# Connector.net
KiCad netlist of a schematic drawn in Altium Designer
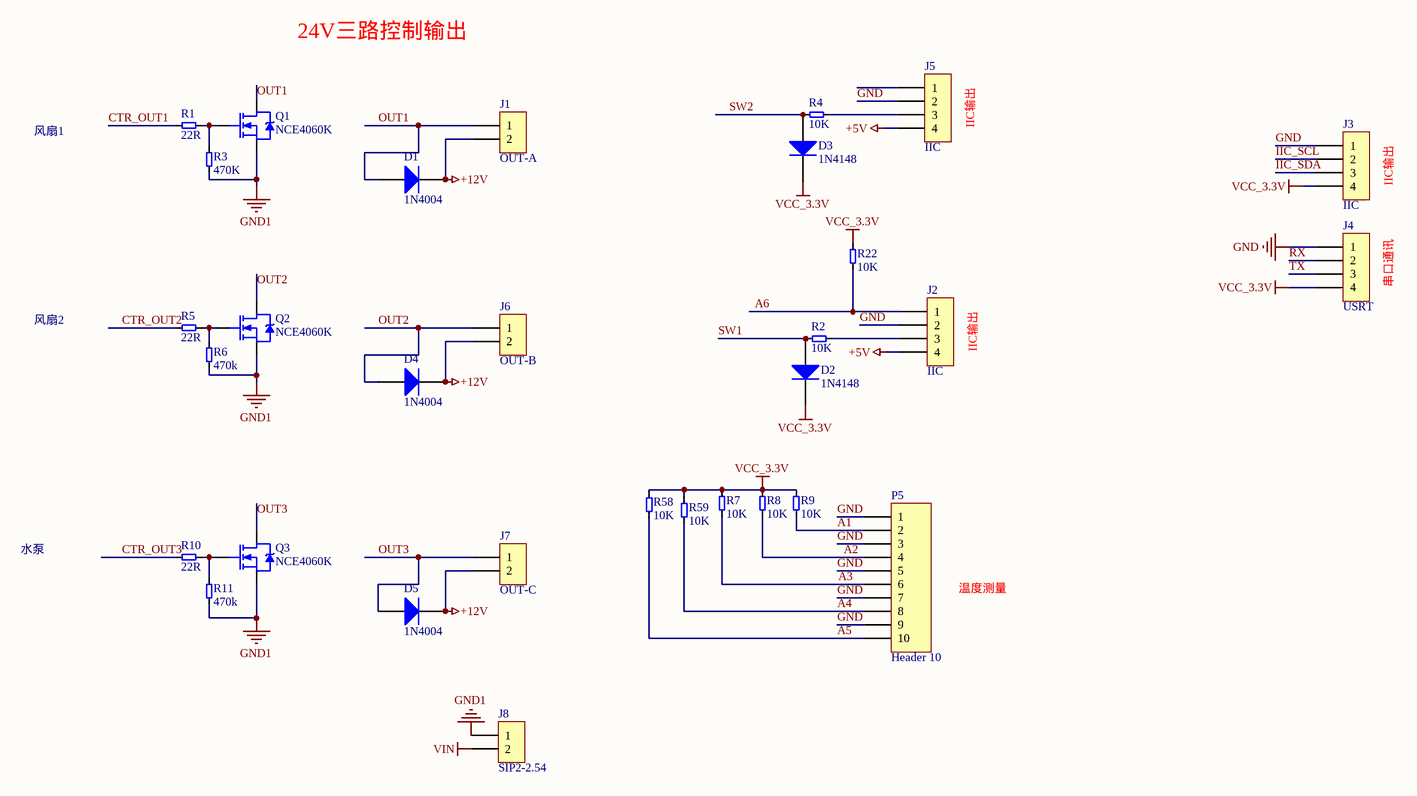
[diagram p0: Connector.SchDoc]

(export (version "E")
  (design (tool "Eeschema 10.0.6"))
  (components
    (comp (ref "D1")
      (value "1N4004")
      (footprint "D7227")
      (description "Default Diode")
      (fields (field (name "PUBLISHER") "Altium Limited"))
      (libsource (lib "SM") (part "Diode_2"))
    )
    (comp (ref "D2")
      (value "1N4148")
      (footprint "sod323")
      (description "Default Diode")
      (fields (field (name "PUBLISHER") "Altium Limited"))
      (libsource (lib "Miscellaneous Devices") (part "Diode"))
    )
    (comp (ref "D3")
      (value "1N4148")
      (footprint "sod323")
      (description "Default Diode")
      (fields (field (name "PUBLISHER") "Altium Limited"))
      (libsource (lib "Miscellaneous Devices") (part "Diode"))
    )
    (comp (ref "D4")
      (value "1N4004")
      (footprint "D7227")
      (description "Default Diode")
      (fields (field (name "PUBLISHER") "Altium Limited"))
      (libsource (lib "SM") (part "Diode_2"))
    )
    (comp (ref "D5")
      (value "1N4004")
      (footprint "D7227")
      (description "Default Diode")
      (fields (field (name "PUBLISHER") "Altium Limited"))
      (libsource (lib "SM") (part "Diode_2"))
    )
    (comp (ref "J1")
      (value "OUT-A")
      (footprint "CH3.96-2P")
      (description "Connector")
      (libsource (lib "SM") (part "CON2"))
    )
    (comp (ref "J2")
      (value "IIC")
      (footprint "SIP-4L")
      (description "CN-SIP4-2.54")
      (libsource (lib "接插件") (part "SIP4-2.54"))
    )
    (comp (ref "J3")
      (value "IIC")
      (footprint "SIP-4L")
      (description "CN-SIP4-2.54")
      (libsource (lib "接插件") (part "SIP4-2.54"))
    )
    (comp (ref "J4")
      (value "USRT")
      (footprint "SIP-4L")
      (description "CN-SIP4-2.54")
      (libsource (lib "接插件") (part "SIP4-2.54"))
    )
    (comp (ref "J5")
      (value "IIC")
      (footprint "SIP-4L")
      (description "CN-SIP4-2.54")
      (libsource (lib "接插件") (part "SIP4-2.54"))
    )
    (comp (ref "J6")
      (value "OUT-B")
      (footprint "CH3.96-2P")
      (description "Connector")
      (libsource (lib "SM") (part "CON2"))
    )
    (comp (ref "J7")
      (value "OUT-C")
      (footprint "CH3.96-2P")
      (description "Connector")
      (libsource (lib "SM") (part "CON2"))
    )
    (comp (ref "J8")
      (value "SIP2-2.54")
      (footprint "CH3.96-2P")
      (description "CN-SIP2-2.54")
      (libsource (lib "接插件") (part "SIP2-2.54"))
    )
    (comp (ref "P5")
      (value "Header 10")
      (footprint "SIP-10L")
      (description "Header, 10-Pin")
      (fields (field (name "PUBLISHER") "Altium Limited"))
      (libsource (lib "Miscellaneous Connectors") (part "Header 10"))
    )
    (comp (ref "Q1")
      (value "NCE4060K")
      (footprint "TO-252-3S")
      (description "NMOSFET")
      (libsource (lib "SM") (part "NCE4060K"))
    )
    (comp (ref "Q2")
      (value "NCE4060K")
      (footprint "TO-252-3S")
      (description "NMOSFET")
      (libsource (lib "SM") (part "NCE4060K"))
    )
    (comp (ref "Q3")
      (value "NCE4060K")
      (footprint "TO-252-3S")
      (description "NMOSFET")
      (libsource (lib "SM") (part "NCE4060K"))
    )
    (comp (ref "R1")
      (value "22R")
      (footprint "0805R")
      (description "CR85-102J")
      (libsource (lib "SMD电阻") (part "1K"))
    )
    (comp (ref "R2")
      (value "10K")
      (footprint "0805R")
      (description "CR85-102J")
      (libsource (lib "SMD电阻") (part "1K"))
    )
    (comp (ref "R3")
      (value "470K")
      (footprint "0805R")
      (description "CR85-102J")
      (libsource (lib "SMD电阻") (part "1K"))
    )
    (comp (ref "R4")
      (value "10K")
      (footprint "0805R")
      (description "CR85-102J")
      (libsource (lib "SMD电阻") (part "1K"))
    )
    (comp (ref "R5")
      (value "22R")
      (footprint "0805R")
      (description "CR85-102J")
      (libsource (lib "SMD电阻") (part "1K"))
    )
    (comp (ref "R6")
      (value "470k")
      (footprint "0805R")
      (description "CR85-102J")
      (libsource (lib "SMD电阻") (part "1K"))
    )
    (comp (ref "R7")
      (value "10K")
      (footprint "0805R")
      (description "CR85-102J")
      (libsource (lib "SMD电阻") (part "1K"))
    )
    (comp (ref "R8")
      (value "10K")
      (footprint "0805R")
      (description "CR85-102J")
      (libsource (lib "SMD电阻") (part "1K"))
    )
    (comp (ref "R9")
      (value "10K")
      (footprint "0805R")
      (description "CR85-102J")
      (libsource (lib "SMD电阻") (part "1K"))
    )
    (comp (ref "R10")
      (value "22R")
      (footprint "0805R")
      (description "CR85-102J")
      (libsource (lib "SMD电阻") (part "1K"))
    )
    (comp (ref "R11")
      (value "470k")
      (footprint "0805R")
      (description "CR85-102J")
      (libsource (lib "SMD电阻") (part "1K"))
    )
    (comp (ref "R22")
      (value "10K")
      (footprint "0805R")
      (description "CR85-102J")
      (libsource (lib "SMD电阻") (part "1K"))
    )
    (comp (ref "R58")
      (value "10K")
      (footprint "0805R")
      (description "CR85-102J")
      (libsource (lib "SMD电阻") (part "1K"))
    )
    (comp (ref "R59")
      (value "10K")
      (footprint "0805R")
      (description "CR85-102J")
      (libsource (lib "SMD电阻") (part "1K"))
    )
  )
  (nets
    (net (code "1") (name "+5V") (class "Default")
      (node (ref "J2") (pin "4") (pinfunction "4_4") (pintype "passive"))
      (node (ref "J5") (pin "4") (pinfunction "4_4") (pintype "passive"))
    )
    (net (code "2") (name "+12V") (class "Default")
      (node (ref "D1") (pin "K") (pinfunction "K_K") (pintype "passive"))
      (node (ref "D4") (pin "K") (pinfunction "K_K") (pintype "passive"))
      (node (ref "D5") (pin "K") (pinfunction "K_K") (pintype "passive"))
      (node (ref "J1") (pin "2") (pinfunction "2_2") (pintype "passive"))
      (node (ref "J6") (pin "2") (pinfunction "2_2") (pintype "passive"))
      (node (ref "J7") (pin "2") (pinfunction "2_2") (pintype "passive"))
    )
    (net (code "3") (name "/A1") (class "Default")
      (node (ref "P5") (pin "2") (pinfunction "2_2") (pintype "passive"))
      (node (ref "R9") (pin "1") (pinfunction "1_1") (pintype "passive"))
    )
    (net (code "4") (name "/A2") (class "Default")
      (node (ref "P5") (pin "4") (pinfunction "4_4") (pintype "passive"))
      (node (ref "R8") (pin "1") (pinfunction "1_1") (pintype "passive"))
    )
    (net (code "5") (name "/A3") (class "Default")
      (node (ref "P5") (pin "6") (pinfunction "6_6") (pintype "passive"))
      (node (ref "R7") (pin "1") (pinfunction "1_1") (pintype "passive"))
    )
    (net (code "6") (name "/A4") (class "Default")
      (node (ref "P5") (pin "8") (pinfunction "8_8") (pintype "passive"))
      (node (ref "R59") (pin "2") (pinfunction "2_2") (pintype "passive"))
    )
    (net (code "7") (name "/A5") (class "Default")
      (node (ref "P5") (pin "10") (pinfunction "10_10") (pintype "passive"))
      (node (ref "R58") (pin "1") (pinfunction "1_1") (pintype "passive"))
    )
    (net (code "8") (name "/A6") (class "Default")
      (node (ref "J2") (pin "1") (pinfunction "1_1") (pintype "passive"))
      (node (ref "R22") (pin "1") (pinfunction "1_1") (pintype "passive"))
    )
    (net (code "9") (name "/CTR_OUT1") (class "Default")
      (node (ref "R1") (pin "1") (pinfunction "1_1") (pintype "passive"))
    )
    (net (code "10") (name "/CTR_OUT2") (class "Default")
      (node (ref "R5") (pin "1") (pinfunction "1_1") (pintype "passive"))
    )
    (net (code "11") (name "/CTR_OUT3") (class "Default")
      (node (ref "R10") (pin "1") (pinfunction "1_1") (pintype "passive"))
    )
    (net (code "12") (name "/IIC_SCL") (class "Default")
      (node (ref "J3") (pin "2") (pinfunction "2_2") (pintype "passive"))
    )
    (net (code "13") (name "/IIC_SDA") (class "Default")
      (node (ref "J3") (pin "3") (pinfunction "3_3") (pintype "passive"))
    )
    (net (code "14") (name "/OUT1") (class "Default")
      (node (ref "D1") (pin "A") (pinfunction "A_A") (pintype "passive"))
      (node (ref "J1") (pin "1") (pinfunction "1_1") (pintype "passive"))
      (node (ref "Q1") (pin "2") (pinfunction "D_2") (pintype "passive"))
    )
    (net (code "15") (name "/OUT2") (class "Default")
      (node (ref "D4") (pin "A") (pinfunction "A_A") (pintype "passive"))
      (node (ref "J6") (pin "1") (pinfunction "1_1") (pintype "passive"))
      (node (ref "Q2") (pin "2") (pinfunction "D_2") (pintype "passive"))
    )
    (net (code "16") (name "/OUT3") (class "Default")
      (node (ref "D5") (pin "A") (pinfunction "A_A") (pintype "passive"))
      (node (ref "J7") (pin "1") (pinfunction "1_1") (pintype "passive"))
      (node (ref "Q3") (pin "2") (pinfunction "D_2") (pintype "passive"))
    )
    (net (code "17") (name "/RX") (class "Default")
      (node (ref "J4") (pin "2") (pinfunction "2_2") (pintype "passive"))
    )
    (net (code "18") (name "/SW1") (class "Default")
      (node (ref "D2") (pin "A") (pinfunction "A_A") (pintype "passive"))
      (node (ref "R2") (pin "2") (pinfunction "2_2") (pintype "passive"))
    )
    (net (code "19") (name "/SW2") (class "Default")
      (node (ref "D3") (pin "A") (pinfunction "A_A") (pintype "passive"))
      (node (ref "R4") (pin "2") (pinfunction "2_2") (pintype "passive"))
    )
    (net (code "20") (name "/TX") (class "Default")
      (node (ref "J4") (pin "3") (pinfunction "3_3") (pintype "passive"))
    )
    (net (code "21") (name "GND") (class "Default")
      (node (ref "J2") (pin "2") (pinfunction "2_2") (pintype "passive"))
      (node (ref "J3") (pin "1") (pinfunction "1_1") (pintype "passive"))
      (node (ref "J4") (pin "1") (pinfunction "1_1") (pintype "passive"))
      (node (ref "J5") (pin "2") (pinfunction "2_2") (pintype "passive"))
      (node (ref "P5") (pin "1") (pinfunction "1_1") (pintype "passive"))
      (node (ref "P5") (pin "3") (pinfunction "3_3") (pintype "passive"))
      (node (ref "P5") (pin "5") (pinfunction "5_5") (pintype "passive"))
      (node (ref "P5") (pin "7") (pinfunction "7_7") (pintype "passive"))
      (node (ref "P5") (pin "9") (pinfunction "9_9") (pintype "passive"))
    )
    (net (code "22") (name "GND1") (class "Default")
      (node (ref "J8") (pin "1") (pinfunction "1_1") (pintype "passive"))
      (node (ref "Q1") (pin "3") (pinfunction "S_3") (pintype "passive"))
      (node (ref "Q2") (pin "3") (pinfunction "S_3") (pintype "passive"))
      (node (ref "Q3") (pin "3") (pinfunction "S_3") (pintype "passive"))
      (node (ref "R11") (pin "1") (pinfunction "1_1") (pintype "passive"))
      (node (ref "R3") (pin "1") (pinfunction "1_1") (pintype "passive"))
      (node (ref "R6") (pin "1") (pinfunction "1_1") (pintype "passive"))
    )
    (net (code "23") (name "Net-(J2-Pad3)") (class "Default")
      (node (ref "J2") (pin "3") (pinfunction "3_3") (pintype "passive"))
      (node (ref "R2") (pin "1") (pinfunction "1_1") (pintype "passive"))
    )
    (net (code "24") (name "Net-(J5-Pad3)") (class "Default")
      (node (ref "J5") (pin "3") (pinfunction "3_3") (pintype "passive"))
      (node (ref "R4") (pin "1") (pinfunction "1_1") (pintype "passive"))
    )
    (net (code "25") (name "Net-(Q1-G)") (class "Default")
      (node (ref "Q1") (pin "1") (pinfunction "G_1") (pintype "passive"))
      (node (ref "R1") (pin "2") (pinfunction "2_2") (pintype "passive"))
      (node (ref "R3") (pin "2") (pinfunction "2_2") (pintype "passive"))
    )
    (net (code "26") (name "Net-(Q2-G)") (class "Default")
      (node (ref "Q2") (pin "1") (pinfunction "G_1") (pintype "passive"))
      (node (ref "R5") (pin "2") (pinfunction "2_2") (pintype "passive"))
      (node (ref "R6") (pin "2") (pinfunction "2_2") (pintype "passive"))
    )
    (net (code "27") (name "Net-(Q3-G)") (class "Default")
      (node (ref "Q3") (pin "1") (pinfunction "G_1") (pintype "passive"))
      (node (ref "R10") (pin "2") (pinfunction "2_2") (pintype "passive"))
      (node (ref "R11") (pin "2") (pinfunction "2_2") (pintype "passive"))
    )
    (net (code "28") (name "VCC_3.3V") (class "Default")
      (node (ref "D2") (pin "K") (pinfunction "K_K") (pintype "passive"))
      (node (ref "D3") (pin "K") (pinfunction "K_K") (pintype "passive"))
      (node (ref "J3") (pin "4") (pinfunction "4_4") (pintype "passive"))
      (node (ref "J4") (pin "4") (pinfunction "4_4") (pintype "passive"))
      (node (ref "R22") (pin "2") (pinfunction "2_2") (pintype "passive"))
      (node (ref "R58") (pin "2") (pinfunction "2_2") (pintype "passive"))
      (node (ref "R59") (pin "1") (pinfunction "1_1") (pintype "passive"))
      (node (ref "R7") (pin "2") (pinfunction "2_2") (pintype "passive"))
      (node (ref "R8") (pin "2") (pinfunction "2_2") (pintype "passive"))
      (node (ref "R9") (pin "2") (pinfunction "2_2") (pintype "passive"))
    )
    (net (code "29") (name "VIN") (class "Default")
      (node (ref "J8") (pin "2") (pinfunction "2_2") (pintype "passive"))
    )
    (net (code "30") (name "unconnected-(J5-Pad1)") (class "Default")
      (node (ref "J5") (pin "1") (pinfunction "1_1") (pintype "passive"))
    )
  )
)
